# Sheet1.net
KiCad netlist of a schematic drawn in Altium Designer
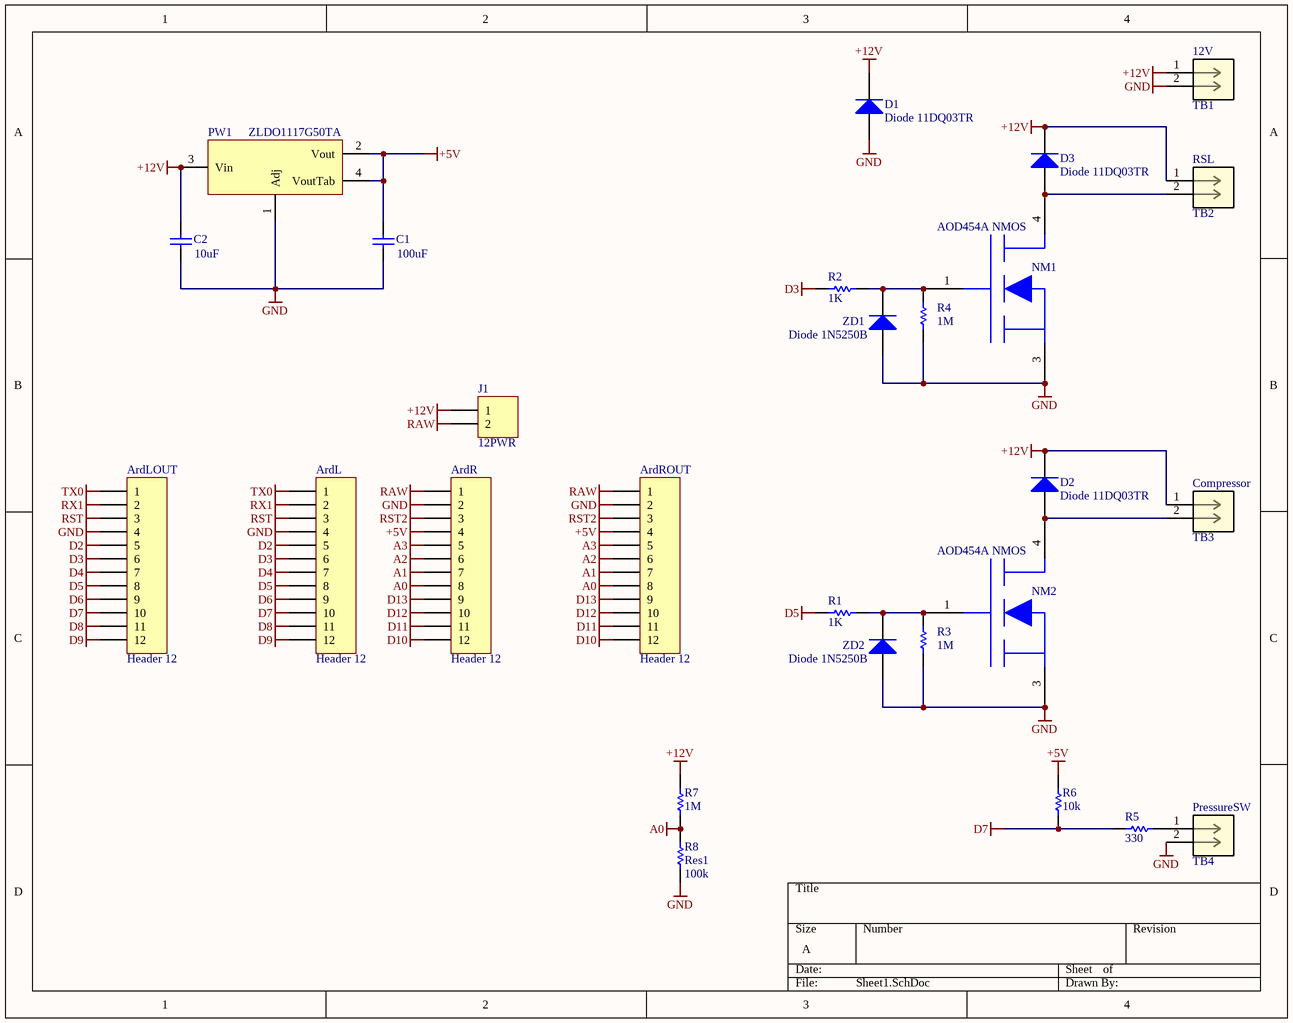
[diagram p0: Sheet1.SchDoc]

(export (version "E")
  (design (tool "Eeschema 10.0.6"))
  (components
    (comp (ref "12V")
      (value "TB1")
      (footprint "CONN_1935161_PXC")
      (description "No Description Available")
      (libsource (lib "1935161") (part "1935161"))
    )
    (comp (ref "ArdL")
      (value "Header 12")
      (footprint "HDR1X12")
      (description "Header, 12-Pin")
      (fields (field (name "PUBLISHER") "Altium Limited"))
      (libsource (lib "Miscellaneous Connectors") (part "Header 12"))
    )
    (comp (ref "ArdLOUT")
      (value "Header 12")
      (footprint "HDR1X12")
      (description "Header, 12-Pin")
      (fields (field (name "PUBLISHER") "Altium Limited"))
      (libsource (lib "Miscellaneous Connectors") (part "Header 12"))
    )
    (comp (ref "ArdR")
      (value "Header 12")
      (footprint "HDR1X12")
      (description "Header, 12-Pin")
      (fields (field (name "PUBLISHER") "Altium Limited"))
      (libsource (lib "Miscellaneous Connectors") (part "Header 12"))
    )
    (comp (ref "ArdROUT")
      (value "Header 12")
      (footprint "HDR1X12")
      (description "Header, 12-Pin")
      (fields (field (name "PUBLISHER") "Altium Limited"))
      (libsource (lib "Miscellaneous Connectors") (part "Header 12"))
    )
    (comp (ref "C1")
      (value "100uF")
      (footprint "CAPC3216L")
      (description "Capacitor (Semiconductor SIM Model)")
      (fields (field (name "Comment") "Cap Semi") (field (name "PUBLISHER") "Altium Limited"))
      (libsource (lib "Miscellaneous Devices") (part "Cap Semi"))
    )
    (comp (ref "C2")
      (value "10uF")
      (footprint "CAPC3216L")
      (description "Capacitor (Semiconductor SIM Model)")
      (fields (field (name "Comment") "Cap Semi") (field (name "PUBLISHER") "Altium Limited"))
      (libsource (lib "Miscellaneous Devices") (part "Cap Semi"))
    )
    (comp (ref "Compressor")
      (value "TB3")
      (footprint "CONN_1935161_PXC")
      (description "No Description Available")
      (libsource (lib "1935161") (part "1935161"))
    )
    (comp (ref "D1")
      (value "Diode 11DQ03TR")
      (footprint "DIO10.46-5.3x2.8")
      (description "1 Amp Fast Recovery Rectifier")
      (fields (field (name "PUBLISHER") "Altium Limited"))
      (libsource (lib "Miscellaneous Devices") (part "Diode 1N4934"))
    )
    (comp (ref "D2")
      (value "Diode 11DQ03TR")
      (footprint "DIO10.46-5.3x2.8")
      (description "1 Amp Fast Recovery Rectifier")
      (fields (field (name "PUBLISHER") "Altium Limited"))
      (libsource (lib "Miscellaneous Devices") (part "Diode 1N4934"))
    )
    (comp (ref "D3")
      (value "Diode 11DQ03TR")
      (footprint "DIO10.46-5.3x2.8")
      (description "1 Amp Fast Recovery Rectifier")
      (fields (field (name "PUBLISHER") "Altium Limited"))
      (libsource (lib "Miscellaneous Devices") (part "Diode 1N4934"))
    )
    (comp (ref "J1")
      (value "12PWR")
      (footprint "HDR1X2")
      (description "Header, 2-Pin")
      (fields (field (name "PUBLISHER") "Altium Limited"))
      (libsource (lib "Miscellaneous Connectors") (part "Header 2"))
    )
    (comp (ref "NM1")
      (value "AOD454A NMOS")
      (footprint "TO252- no center pin")
      (libsource (lib "Launcher Custom Footprints") (part "AOD454A NMOS"))
    )
    (comp (ref "NM2")
      (value "AOD454A NMOS")
      (footprint "TO252- no center pin")
      (libsource (lib "Launcher Custom Footprints") (part "AOD454A NMOS"))
    )
    (comp (ref "PressureSW")
      (value "TB4")
      (footprint "CONN_1935161_PXC")
      (description "No Description Available")
      (libsource (lib "1935161") (part "1935161"))
    )
    (comp (ref "PW1")
      (value "ZLDO1117G50TA")
      (footprint "SOT223")
      (libsource (lib "Launcher Custom Footprints") (part "ZLDO1117G50TA"))
    )
    (comp (ref "R1")
      (value "1K")
      (footprint "RESC3216L")
      (description "Semiconductor Resistor")
      (fields (field (name "Comment") "Res Semi") (field (name "PUBLISHER") "Altium Limited"))
      (libsource (lib "Miscellaneous Devices") (part "Res Semi"))
    )
    (comp (ref "R2")
      (value "1K")
      (footprint "RESC3216L")
      (description "Semiconductor Resistor")
      (fields (field (name "Comment") "Res Semi") (field (name "PUBLISHER") "Altium Limited"))
      (libsource (lib "Miscellaneous Devices") (part "Res Semi"))
    )
    (comp (ref "R3")
      (value "1M")
      (footprint "RESC3216L")
      (description "Semiconductor Resistor")
      (fields (field (name "Comment") "Res Semi") (field (name "PUBLISHER") "Altium Limited"))
      (libsource (lib "Miscellaneous Devices") (part "Res Semi"))
    )
    (comp (ref "R4")
      (value "1M")
      (footprint "RESC3216L")
      (description "Semiconductor Resistor")
      (fields (field (name "Comment") "Res Semi") (field (name "PUBLISHER") "Altium Limited"))
      (libsource (lib "Miscellaneous Devices") (part "Res Semi"))
    )
    (comp (ref "R5")
      (value "330")
      (footprint "RESC3216L")
      (description "Semiconductor Resistor")
      (fields (field (name "Comment") "Res Semi") (field (name "PUBLISHER") "Altium Limited"))
      (libsource (lib "Miscellaneous Devices") (part "Res Semi"))
    )
    (comp (ref "R6")
      (value "10k")
      (footprint "RESC3216L")
      (description "Semiconductor Resistor")
      (fields (field (name "Comment") "Res Semi") (field (name "PUBLISHER") "Altium Limited"))
      (libsource (lib "Miscellaneous Devices") (part "Res Semi"))
    )
    (comp (ref "R7")
      (value "1M")
      (footprint "AXIAL-0.3")
      (description "Resistor")
      (fields (field (name "PUBLISHER") "Altium Limited"))
      (libsource (lib "Miscellaneous Devices") (part "Res1"))
    )
    (comp (ref "R8")
      (value "Res1")
      (footprint "AXIAL-0.3")
      (description "Resistor")
      (fields (field (name "ALTIUM_VALUE") "100k") (field (name "PUBLISHER") "Altium Limited"))
      (libsource (lib "Miscellaneous Devices") (part "Res1"))
    )
    (comp (ref "RSL")
      (value "TB2")
      (footprint "CONN_1935161_PXC")
      (description "No Description Available")
      (libsource (lib "1935161") (part "1935161"))
    )
    (comp (ref "ZD1")
      (value "Diode 1N5250B")
      (footprint "DIO7.1-3.9x1.9")
      (description "High Conductance Fast Diode")
      (fields (field (name "PUBLISHER") "Altium Limited"))
      (libsource (lib "Miscellaneous Devices") (part "Diode 1N4448"))
    )
    (comp (ref "ZD2")
      (value "Diode 1N5250B")
      (footprint "DIO7.1-3.9x1.9")
      (description "High Conductance Fast Diode")
      (fields (field (name "PUBLISHER") "Altium Limited"))
      (libsource (lib "Miscellaneous Devices") (part "Diode 1N4448"))
    )
  )
  (nets
    (net (code "1") (name "+5V") (class "Default")
      (node (ref "ArdR") (pin "4") (pinfunction "4_4") (pintype "passive"))
      (node (ref "ArdROUT") (pin "4") (pinfunction "4_4") (pintype "passive"))
      (node (ref "C1") (pin "2") (pinfunction "2_2") (pintype "passive"))
      (node (ref "PW1") (pin "2") (pinfunction "Vout_2") (pintype "passive"))
      (node (ref "PW1") (pin "4") (pinfunction "VoutTab_4") (pintype "passive"))
      (node (ref "R6") (pin "1") (pinfunction "1_1") (pintype "passive"))
    )
    (net (code "2") (name "+12V") (class "Default")
      (node (ref "12V") (pin "1") (pinfunction "1_1") (pintype "passive"))
      (node (ref "C2") (pin "2") (pinfunction "2_2") (pintype "passive"))
      (node (ref "Compressor") (pin "1") (pinfunction "1_1") (pintype "passive"))
      (node (ref "D1") (pin "2") (pinfunction "K_2") (pintype "passive"))
      (node (ref "D2") (pin "2") (pinfunction "K_2") (pintype "passive"))
      (node (ref "D3") (pin "2") (pinfunction "K_2") (pintype "passive"))
      (node (ref "J1") (pin "1") (pinfunction "1_1") (pintype "passive"))
      (node (ref "PW1") (pin "3") (pinfunction "Vin_3") (pintype "passive"))
      (node (ref "R7") (pin "2") (pinfunction "2_2") (pintype "passive"))
      (node (ref "RSL") (pin "1") (pinfunction "1_1") (pintype "passive"))
    )
    (net (code "3") (name "A0") (class "Default")
      (node (ref "ArdR") (pin "8") (pinfunction "8_8") (pintype "passive"))
      (node (ref "ArdROUT") (pin "8") (pinfunction "8_8") (pintype "passive"))
      (node (ref "R7") (pin "1") (pinfunction "1_1") (pintype "passive"))
      (node (ref "R8") (pin "2") (pinfunction "2_2") (pintype "passive"))
    )
    (net (code "4") (name "A1") (class "Default")
      (node (ref "ArdR") (pin "7") (pinfunction "7_7") (pintype "passive"))
      (node (ref "ArdROUT") (pin "7") (pinfunction "7_7") (pintype "passive"))
    )
    (net (code "5") (name "A2") (class "Default")
      (node (ref "ArdR") (pin "6") (pinfunction "6_6") (pintype "passive"))
      (node (ref "ArdROUT") (pin "6") (pinfunction "6_6") (pintype "passive"))
    )
    (net (code "6") (name "A3") (class "Default")
      (node (ref "ArdR") (pin "5") (pinfunction "5_5") (pintype "passive"))
      (node (ref "ArdROUT") (pin "5") (pinfunction "5_5") (pintype "passive"))
    )
    (net (code "7") (name "D2") (class "Default")
      (node (ref "ArdL") (pin "5") (pinfunction "5_5") (pintype "passive"))
      (node (ref "ArdLOUT") (pin "5") (pinfunction "5_5") (pintype "passive"))
    )
    (net (code "8") (name "D3") (class "Default")
      (node (ref "ArdL") (pin "6") (pinfunction "6_6") (pintype "passive"))
      (node (ref "ArdLOUT") (pin "6") (pinfunction "6_6") (pintype "passive"))
      (node (ref "R2") (pin "2") (pinfunction "2_2") (pintype "passive"))
    )
    (net (code "9") (name "D4") (class "Default")
      (node (ref "ArdL") (pin "7") (pinfunction "7_7") (pintype "passive"))
      (node (ref "ArdLOUT") (pin "7") (pinfunction "7_7") (pintype "passive"))
    )
    (net (code "10") (name "D5") (class "Default")
      (node (ref "ArdL") (pin "8") (pinfunction "8_8") (pintype "passive"))
      (node (ref "ArdLOUT") (pin "8") (pinfunction "8_8") (pintype "passive"))
      (node (ref "R1") (pin "2") (pinfunction "2_2") (pintype "passive"))
    )
    (net (code "11") (name "D6") (class "Default")
      (node (ref "ArdL") (pin "9") (pinfunction "9_9") (pintype "passive"))
      (node (ref "ArdLOUT") (pin "9") (pinfunction "9_9") (pintype "passive"))
    )
    (net (code "12") (name "D7") (class "Default")
      (node (ref "ArdL") (pin "10") (pinfunction "10_10") (pintype "passive"))
      (node (ref "ArdLOUT") (pin "10") (pinfunction "10_10") (pintype "passive"))
      (node (ref "R5") (pin "2") (pinfunction "2_2") (pintype "passive"))
      (node (ref "R6") (pin "2") (pinfunction "2_2") (pintype "passive"))
    )
    (net (code "13") (name "D8") (class "Default")
      (node (ref "ArdL") (pin "11") (pinfunction "11_11") (pintype "passive"))
      (node (ref "ArdLOUT") (pin "11") (pinfunction "11_11") (pintype "passive"))
    )
    (net (code "14") (name "D9") (class "Default")
      (node (ref "ArdL") (pin "12") (pinfunction "12_12") (pintype "passive"))
      (node (ref "ArdLOUT") (pin "12") (pinfunction "12_12") (pintype "passive"))
    )
    (net (code "15") (name "D10") (class "Default")
      (node (ref "ArdR") (pin "12") (pinfunction "12_12") (pintype "passive"))
      (node (ref "ArdROUT") (pin "12") (pinfunction "12_12") (pintype "passive"))
    )
    (net (code "16") (name "D11") (class "Default")
      (node (ref "ArdR") (pin "11") (pinfunction "11_11") (pintype "passive"))
      (node (ref "ArdROUT") (pin "11") (pinfunction "11_11") (pintype "passive"))
    )
    (net (code "17") (name "D12") (class "Default")
      (node (ref "ArdR") (pin "10") (pinfunction "10_10") (pintype "passive"))
      (node (ref "ArdROUT") (pin "10") (pinfunction "10_10") (pintype "passive"))
    )
    (net (code "18") (name "D13") (class "Default")
      (node (ref "ArdR") (pin "9") (pinfunction "9_9") (pintype "passive"))
      (node (ref "ArdROUT") (pin "9") (pinfunction "9_9") (pintype "passive"))
    )
    (net (code "19") (name "GND") (class "Default")
      (node (ref "12V") (pin "2") (pinfunction "2_2") (pintype "passive"))
      (node (ref "ArdL") (pin "4") (pinfunction "4_4") (pintype "passive"))
      (node (ref "ArdLOUT") (pin "4") (pinfunction "4_4") (pintype "passive"))
      (node (ref "ArdR") (pin "2") (pinfunction "2_2") (pintype "passive"))
      (node (ref "ArdROUT") (pin "2") (pinfunction "2_2") (pintype "passive"))
      (node (ref "C1") (pin "1") (pinfunction "1_1") (pintype "passive"))
      (node (ref "C2") (pin "1") (pinfunction "1_1") (pintype "passive"))
      (node (ref "D1") (pin "1") (pinfunction "A_1") (pintype "passive"))
      (node (ref "NM1") (pin "3") (pinfunction "3_-_Source_3") (pintype "passive"))
      (node (ref "NM2") (pin "3") (pinfunction "3_-_Source_3") (pintype "passive"))
      (node (ref "PW1") (pin "1") (pinfunction "Adj_1") (pintype "passive"))
      (node (ref "PressureSW") (pin "2") (pinfunction "2_2") (pintype "passive"))
      (node (ref "R3") (pin "1") (pinfunction "1_1") (pintype "passive"))
      (node (ref "R4") (pin "1") (pinfunction "1_1") (pintype "passive"))
      (node (ref "R8") (pin "1") (pinfunction "1_1") (pintype "passive"))
      (node (ref "ZD1") (pin "1") (pinfunction "A_1") (pintype "passive"))
      (node (ref "ZD2") (pin "1") (pinfunction "A_1") (pintype "passive"))
    )
    (net (code "20") (name "Net-(D2-A)") (class "Default")
      (node (ref "Compressor") (pin "2") (pinfunction "2_2") (pintype "passive"))
      (node (ref "D2") (pin "1") (pinfunction "A_1") (pintype "passive"))
      (node (ref "NM2") (pin "4") (pinfunction "4_-_Drain_4") (pintype "passive"))
    )
    (net (code "21") (name "Net-(D3-A)") (class "Default")
      (node (ref "D3") (pin "1") (pinfunction "A_1") (pintype "passive"))
      (node (ref "NM1") (pin "4") (pinfunction "4_-_Drain_4") (pintype "passive"))
      (node (ref "RSL") (pin "2") (pinfunction "2_2") (pintype "passive"))
    )
    (net (code "22") (name "Net-(NM1-1_-_Gate)") (class "Default")
      (node (ref "NM1") (pin "1") (pinfunction "1_-_Gate_1") (pintype "passive"))
      (node (ref "R2") (pin "1") (pinfunction "1_1") (pintype "passive"))
      (node (ref "R4") (pin "2") (pinfunction "2_2") (pintype "passive"))
      (node (ref "ZD1") (pin "2") (pinfunction "K_2") (pintype "passive"))
    )
    (net (code "23") (name "Net-(NM2-1_-_Gate)") (class "Default")
      (node (ref "NM2") (pin "1") (pinfunction "1_-_Gate_1") (pintype "passive"))
      (node (ref "R1") (pin "1") (pinfunction "1_1") (pintype "passive"))
      (node (ref "R3") (pin "2") (pinfunction "2_2") (pintype "passive"))
      (node (ref "ZD2") (pin "2") (pinfunction "K_2") (pintype "passive"))
    )
    (net (code "24") (name "Net-(PressureSW-Pad1)") (class "Default")
      (node (ref "PressureSW") (pin "1") (pinfunction "1_1") (pintype "passive"))
      (node (ref "R5") (pin "1") (pinfunction "1_1") (pintype "passive"))
    )
    (net (code "25") (name "RAW") (class "Default")
      (node (ref "ArdR") (pin "1") (pinfunction "1_1") (pintype "passive"))
      (node (ref "ArdROUT") (pin "1") (pinfunction "1_1") (pintype "passive"))
      (node (ref "J1") (pin "2") (pinfunction "2_2") (pintype "passive"))
    )
    (net (code "26") (name "RST") (class "Default")
      (node (ref "ArdL") (pin "3") (pinfunction "3_3") (pintype "passive"))
      (node (ref "ArdLOUT") (pin "3") (pinfunction "3_3") (pintype "passive"))
    )
    (net (code "27") (name "RST2") (class "Default")
      (node (ref "ArdR") (pin "3") (pinfunction "3_3") (pintype "passive"))
      (node (ref "ArdROUT") (pin "3") (pinfunction "3_3") (pintype "passive"))
    )
    (net (code "28") (name "RX1") (class "Default")
      (node (ref "ArdL") (pin "2") (pinfunction "2_2") (pintype "passive"))
      (node (ref "ArdLOUT") (pin "2") (pinfunction "2_2") (pintype "passive"))
    )
    (net (code "29") (name "TX0") (class "Default")
      (node (ref "ArdL") (pin "1") (pinfunction "1_1") (pintype "passive"))
      (node (ref "ArdLOUT") (pin "1") (pinfunction "1_1") (pintype "passive"))
    )
  )
)
